# MCU.net
KiCad netlist of a schematic drawn in Altium Designer
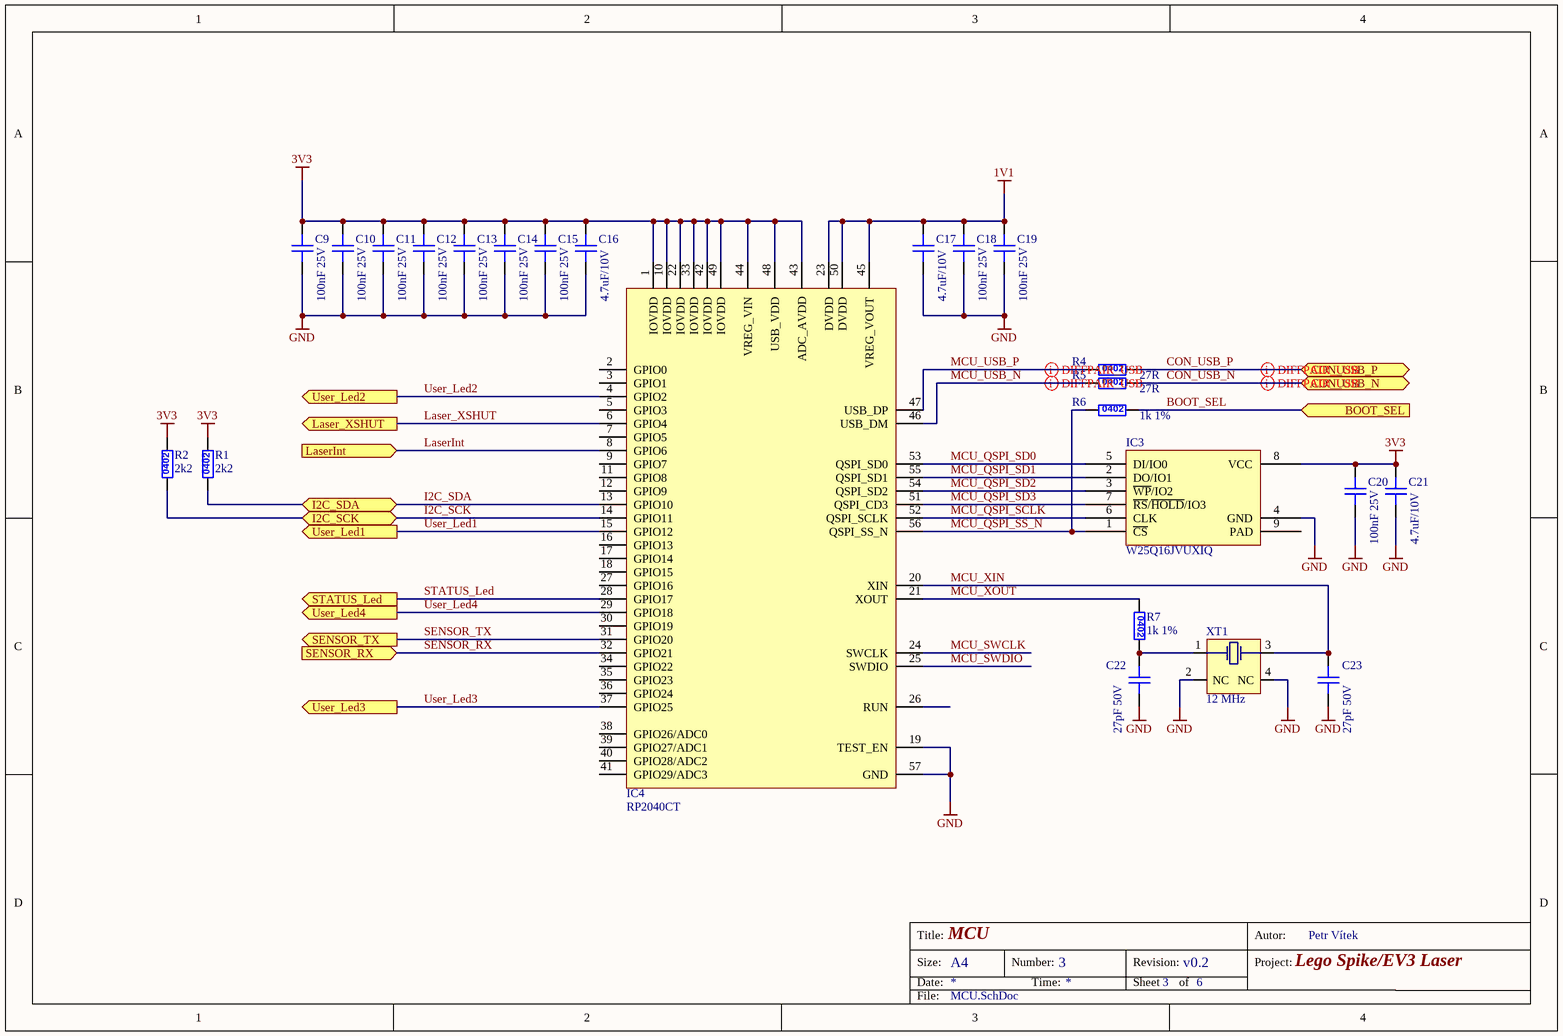
[diagram p0: MCU.SchDoc]

(export (version "E")
  (design (tool "Eeschema 10.0.6"))
  (components
    (comp (ref "C9")
      (value "100nF 25V")
      (footprint "C0402")
      (description "WALSIN - 0402B104K250CT - CAPACITOR, MLCC, X7R, 0.1UF, 25V, 0402")
      (fields (field (name "Comment") "UniversalCapacitor"))
      (libsource (lib "UTBStockLib") (part "UniversalCapacitor"))
    )
    (comp (ref "C10")
      (value "100nF 25V")
      (footprint "C0402")
      (description "WALSIN - 0402B104K250CT - CAPACITOR, MLCC, X7R, 0.1UF, 25V, 0402")
      (fields (field (name "Comment") "UniversalCapacitor"))
      (libsource (lib "UTBStockLib") (part "UniversalCapacitor"))
    )
    (comp (ref "C11")
      (value "100nF 25V")
      (footprint "C0402")
      (description "WALSIN - 0402B104K250CT - CAPACITOR, MLCC, X7R, 0.1UF, 25V, 0402")
      (fields (field (name "Comment") "UniversalCapacitor"))
      (libsource (lib "UTBStockLib") (part "UniversalCapacitor"))
    )
    (comp (ref "C12")
      (value "100nF 25V")
      (footprint "C0402")
      (description "WALSIN - 0402B104K250CT - CAPACITOR, MLCC, X7R, 0.1UF, 25V, 0402")
      (fields (field (name "Comment") "UniversalCapacitor"))
      (libsource (lib "UTBStockLib") (part "UniversalCapacitor"))
    )
    (comp (ref "C13")
      (value "100nF 25V")
      (footprint "C0402")
      (description "WALSIN - 0402B104K250CT - CAPACITOR, MLCC, X7R, 0.1UF, 25V, 0402")
      (fields (field (name "Comment") "UniversalCapacitor"))
      (libsource (lib "UTBStockLib") (part "UniversalCapacitor"))
    )
    (comp (ref "C14")
      (value "100nF 25V")
      (footprint "C0402")
      (description "WALSIN - 0402B104K250CT - CAPACITOR, MLCC, X7R, 0.1UF, 25V, 0402")
      (fields (field (name "Comment") "UniversalCapacitor"))
      (libsource (lib "UTBStockLib") (part "UniversalCapacitor"))
    )
    (comp (ref "C15")
      (value "100nF 25V")
      (footprint "C0402")
      (description "WALSIN - 0402B104K250CT - CAPACITOR, MLCC, X7R, 0.1UF, 25V, 0402")
      (fields (field (name "Comment") "UniversalCapacitor"))
      (libsource (lib "UTBStockLib") (part "UniversalCapacitor"))
    )
    (comp (ref "C16")
      (value "4.7uF/10V")
      (footprint "C0402_big")
      (description "MURATA - GRM155R61A475MEAAD - CAP, MLCC, X5R, 4.7UF, 10V, 0402")
      (libsource (lib "UTBStockLib") (part "UniversalCapacitor"))
    )
    (comp (ref "C17")
      (value "4.7uF/10V")
      (footprint "C0402_big")
      (description "MURATA - GRM155R61A475MEAAD - CAP, MLCC, X5R, 4.7UF, 10V, 0402")
      (libsource (lib "UTBStockLib") (part "UniversalCapacitor"))
    )
    (comp (ref "C18")
      (value "100nF 25V")
      (footprint "C0402")
      (description "WALSIN - 0402B104K250CT - CAPACITOR, MLCC, X7R, 0.1UF, 25V, 0402")
      (fields (field (name "Comment") "UniversalCapacitor"))
      (libsource (lib "UTBStockLib") (part "UniversalCapacitor"))
    )
    (comp (ref "C19")
      (value "100nF 25V")
      (footprint "C0402")
      (description "WALSIN - 0402B104K250CT - CAPACITOR, MLCC, X7R, 0.1UF, 25V, 0402")
      (fields (field (name "Comment") "UniversalCapacitor"))
      (libsource (lib "UTBStockLib") (part "UniversalCapacitor"))
    )
    (comp (ref "C20")
      (value "100nF 25V")
      (footprint "C0402")
      (description "WALSIN - 0402B104K250CT - CAPACITOR, MLCC, X7R, 0.1UF, 25V, 0402")
      (fields (field (name "Comment") "UniversalCapacitor"))
      (libsource (lib "UTBStockLib") (part "UniversalCapacitor"))
    )
    (comp (ref "C21")
      (value "4.7uF/10V")
      (footprint "C0402_big")
      (description "MURATA - GRM155R61A475MEAAD - CAP, MLCC, X5R, 4.7UF, 10V, 0402")
      (libsource (lib "UTBStockLib") (part "UniversalCapacitor"))
    )
    (comp (ref "C22")
      (value "27pF 50V")
      (footprint "C0402")
      (description "WALSIN - 0402N270J500CT - CAPACITOR, MLCC, NP0, 27PF, 50V, 0402")
      (fields (field (name "Comment") "UniversalCapacitor"))
      (libsource (lib "UTBStockLib") (part "UniversalCapacitor"))
    )
    (comp (ref "C23")
      (value "27pF 50V")
      (footprint "C0402")
      (description "WALSIN - 0402N270J500CT - CAPACITOR, MLCC, NP0, 27PF, 50V, 0402")
      (fields (field (name "Comment") "UniversalCapacitor"))
      (libsource (lib "UTBStockLib") (part "UniversalCapacitor"))
    )
    (comp (ref "IC3")
      (value "W25Q16JVUXIQ")
      (footprint "USON-8_3x2")
      (description "Flash NOR spiFlash, 3V, 16M-bit, 4Kb Uniform Sector, DTR")
      (fields (field (name "Comment") "W25Q16JV"))
      (libsource (lib "UTBStockLib") (part "W25Q16JVUXIQ"))
    )
    (comp (ref "IC4")
      (value "RP2040CT")
      (footprint "QFN56")
      (fields (field (name "Comment") "RP2040"))
      (libsource (lib "UTBStockLib") (part "RP2040"))
    )
    (comp (ref "R1")
      (value "2k2")
      (footprint "R0402")
      (description "VISHAY - CRCW04022K20FKED. - RES, THICK FILM, 2K2, 1%, 0.063W, 0402")
      (fields (field (name "Comment") "UniversalResistor0402"))
      (libsource (lib "UTBStockLib") (part "UniversalResistor0402"))
    )
    (comp (ref "R2")
      (value "2k2")
      (footprint "R0402")
      (description "VISHAY - CRCW04022K20FKED. - RES, THICK FILM, 2K2, 1%, 0.063W, 0402")
      (fields (field (name "Comment") "UniversalResistor0402"))
      (libsource (lib "UTBStockLib") (part "UniversalResistor0402"))
    )
    (comp (ref "R4")
      (value "27R")
      (footprint "R0402")
      (fields (field (name "Comment") "UniversalResistor0402"))
      (libsource (lib "UTBStockLib") (part "UniversalResistor0402"))
    )
    (comp (ref "R5")
      (value "27R")
      (footprint "R0402")
      (fields (field (name "Comment") "UniversalResistor0402"))
      (libsource (lib "UTBStockLib") (part "UniversalResistor0402"))
    )
    (comp (ref "R6")
      (value "1k 1%")
      (footprint "R0402")
      (description "VISHAY - CRCW04021K00FKED - RES, THICK FILM, 1K, 1%, 0.063W, 0402")
      (fields (field (name "Comment") "UniversalResistor0402"))
      (libsource (lib "UTBStockLib") (part "UniversalResistor0402"))
    )
    (comp (ref "R7")
      (value "1k 1%")
      (footprint "R0402")
      (description "VISHAY - CRCW04021K00FKED - RES, THICK FILM, 1K, 1%, 0.063W, 0402")
      (fields (field (name "Comment") "UniversalResistor0402"))
      (libsource (lib "UTBStockLib") (part "UniversalResistor0402"))
    )
    (comp (ref "XT1")
      (value "12 MHz")
      (footprint "ABM8")
      (description "Krystaly 12.0 MHZ 18PF 20PPM 120OHM")
      (fields (field (name "Comment") "XTAL-4Pads-2Used"))
      (libsource (lib "UTBStockLib") (part "XTAL-4Pads-2Used"))
    )
  )
  (nets
    (net (code "1") (name "/BOOT_SEL") (class "Default")
      (node (ref "R6") (pin "1") (pinfunction "1_1") (pintype "passive"))
    )
    (net (code "2") (name "/CON_USB_N") (class "Default")
      (node (ref "R5") (pin "1") (pinfunction "1_1") (pintype "passive"))
    )
    (net (code "3") (name "/CON_USB_P") (class "Default")
      (node (ref "R4") (pin "1") (pinfunction "1_1") (pintype "passive"))
    )
    (net (code "4") (name "/I2C_SCK") (class "Default")
      (node (ref "IC4") (pin "14") (pinfunction "GPIO11_14") (pintype "passive"))
      (node (ref "R2") (pin "2") (pinfunction "2_2") (pintype "passive"))
    )
    (net (code "5") (name "/I2C_SDA") (class "Default")
      (node (ref "IC4") (pin "13") (pinfunction "GPIO10_13") (pintype "passive"))
      (node (ref "R1") (pin "2") (pinfunction "2_2") (pintype "passive"))
    )
    (net (code "6") (name "/LaserInt") (class "Default")
      (node (ref "IC4") (pin "8") (pinfunction "GPIO6_8") (pintype "passive"))
    )
    (net (code "7") (name "/Laser_XSHUT") (class "Default")
      (node (ref "IC4") (pin "6") (pinfunction "GPIO4_6") (pintype "passive"))
    )
    (net (code "8") (name "/MCU_QSPI_SCLK") (class "Default")
      (node (ref "IC3") (pin "6") (pinfunction "CLK_6") (pintype "passive"))
      (node (ref "IC4") (pin "52") (pinfunction "QSPI_SCLK_52") (pintype "passive"))
    )
    (net (code "9") (name "/MCU_QSPI_SD0") (class "Default")
      (node (ref "IC3") (pin "5") (pinfunction "DI/IO0_5") (pintype "passive"))
      (node (ref "IC4") (pin "53") (pinfunction "QSPI_SD0_53") (pintype "passive"))
    )
    (net (code "10") (name "/MCU_QSPI_SD1") (class "Default")
      (node (ref "IC3") (pin "2") (pinfunction "DO/IO1_2") (pintype "passive"))
      (node (ref "IC4") (pin "55") (pinfunction "QSPI_SD1_55") (pintype "passive"))
    )
    (net (code "11") (name "/MCU_QSPI_SD2") (class "Default")
      (node (ref "IC3") (pin "3") (pinfunction "~{WP}/IO2_3") (pintype "passive"))
      (node (ref "IC4") (pin "54") (pinfunction "QSPI_SD2_54") (pintype "passive"))
    )
    (net (code "12") (name "/MCU_QSPI_SD3") (class "Default")
      (node (ref "IC3") (pin "7") (pinfunction "~{RS}/~{HOLD}/IO3_7") (pintype "passive"))
      (node (ref "IC4") (pin "51") (pinfunction "QSPI_CD3_51") (pintype "passive"))
    )
    (net (code "13") (name "/MCU_QSPI_SS_N") (class "Default")
      (node (ref "IC3") (pin "1") (pinfunction "~{CS}_1") (pintype "passive"))
      (node (ref "IC4") (pin "56") (pinfunction "QSPI_SS_N_56") (pintype "passive"))
      (node (ref "R6") (pin "2") (pinfunction "2_2") (pintype "passive"))
    )
    (net (code "14") (name "/MCU_SWCLK") (class "Default")
      (node (ref "IC4") (pin "24") (pinfunction "SWCLK_24") (pintype "passive"))
    )
    (net (code "15") (name "/MCU_SWDIO") (class "Default")
      (node (ref "IC4") (pin "25") (pinfunction "SWDIO_25") (pintype "passive"))
    )
    (net (code "16") (name "/MCU_USB_N") (class "Default")
      (node (ref "IC4") (pin "46") (pinfunction "USB_DM_46") (pintype "passive"))
      (node (ref "R5") (pin "2") (pinfunction "2_2") (pintype "passive"))
    )
    (net (code "17") (name "/MCU_USB_P") (class "Default")
      (node (ref "IC4") (pin "47") (pinfunction "USB_DP_47") (pintype "passive"))
      (node (ref "R4") (pin "2") (pinfunction "2_2") (pintype "passive"))
    )
    (net (code "18") (name "/MCU_XIN") (class "Default")
      (node (ref "C23") (pin "1") (pinfunction "1_1") (pintype "passive"))
      (node (ref "IC4") (pin "20") (pinfunction "XIN_20") (pintype "passive"))
      (node (ref "XT1") (pin "3") (pintype "passive"))
    )
    (net (code "19") (name "/MCU_XOUT") (class "Default")
      (node (ref "IC4") (pin "21") (pinfunction "XOUT_21") (pintype "passive"))
      (node (ref "R7") (pin "2") (pinfunction "2_2") (pintype "passive"))
    )
    (net (code "20") (name "/SENSOR_RX") (class "Default")
      (node (ref "IC4") (pin "32") (pinfunction "GPIO21_32") (pintype "passive"))
    )
    (net (code "21") (name "/SENSOR_TX") (class "Default")
      (node (ref "IC4") (pin "31") (pinfunction "GPIO20_31") (pintype "passive"))
    )
    (net (code "22") (name "/STATUS_Led") (class "Default")
      (node (ref "IC4") (pin "28") (pinfunction "GPIO17_28") (pintype "passive"))
    )
    (net (code "23") (name "/User_Led1") (class "Default")
      (node (ref "IC4") (pin "15") (pinfunction "GPIO12_15") (pintype "passive"))
    )
    (net (code "24") (name "/User_Led2") (class "Default")
      (node (ref "IC4") (pin "4") (pinfunction "GPIO2_4") (pintype "passive"))
    )
    (net (code "25") (name "/User_Led3") (class "Default")
      (node (ref "IC4") (pin "37") (pinfunction "GPIO25_37") (pintype "passive"))
    )
    (net (code "26") (name "/User_Led4") (class "Default")
      (node (ref "IC4") (pin "29") (pinfunction "GPIO18_29") (pintype "passive"))
    )
    (net (code "27") (name "1V1") (class "Default")
      (node (ref "C17") (pin "1") (pinfunction "1_1") (pintype "passive"))
      (node (ref "C18") (pin "2") (pinfunction "2_2") (pintype "passive"))
      (node (ref "C19") (pin "2") (pinfunction "2_2") (pintype "passive"))
      (node (ref "IC4") (pin "23") (pinfunction "DVDD_23") (pintype "passive"))
      (node (ref "IC4") (pin "45") (pinfunction "VREG_VOUT_45") (pintype "passive"))
      (node (ref "IC4") (pin "50") (pinfunction "DVDD_50") (pintype "passive"))
    )
    (net (code "28") (name "3V3") (class "Default")
      (node (ref "C10") (pin "2") (pinfunction "2_2") (pintype "passive"))
      (node (ref "C11") (pin "2") (pinfunction "2_2") (pintype "passive"))
      (node (ref "C12") (pin "2") (pinfunction "2_2") (pintype "passive"))
      (node (ref "C13") (pin "2") (pinfunction "2_2") (pintype "passive"))
      (node (ref "C14") (pin "2") (pinfunction "2_2") (pintype "passive"))
      (node (ref "C15") (pin "2") (pinfunction "2_2") (pintype "passive"))
      (node (ref "C16") (pin "1") (pinfunction "1_1") (pintype "passive"))
      (node (ref "C20") (pin "2") (pinfunction "2_2") (pintype "passive"))
      (node (ref "C21") (pin "1") (pinfunction "1_1") (pintype "passive"))
      (node (ref "C9") (pin "2") (pinfunction "2_2") (pintype "passive"))
      (node (ref "IC3") (pin "8") (pinfunction "VCC_8") (pintype "passive"))
      (node (ref "IC4") (pin "1") (pinfunction "IOVDD_1") (pintype "passive"))
      (node (ref "IC4") (pin "10") (pinfunction "IOVDD_10") (pintype "passive"))
      (node (ref "IC4") (pin "22") (pinfunction "IOVDD_22") (pintype "passive"))
      (node (ref "IC4") (pin "33") (pinfunction "IOVDD_33") (pintype "passive"))
      (node (ref "IC4") (pin "42") (pinfunction "IOVDD_42") (pintype "passive"))
      (node (ref "IC4") (pin "43") (pinfunction "ADC_AVDD_43") (pintype "passive"))
      (node (ref "IC4") (pin "44") (pinfunction "VREG_VIN_44") (pintype "passive"))
      (node (ref "IC4") (pin "48") (pinfunction "USB_VDD_48") (pintype "passive"))
      (node (ref "IC4") (pin "49") (pinfunction "IOVDD_49") (pintype "passive"))
      (node (ref "R1") (pin "1") (pinfunction "1_1") (pintype "passive"))
      (node (ref "R2") (pin "1") (pinfunction "1_1") (pintype "passive"))
    )
    (net (code "29") (name "GND") (class "Default")
      (node (ref "C10") (pin "1") (pinfunction "1_1") (pintype "passive"))
      (node (ref "C11") (pin "1") (pinfunction "1_1") (pintype "passive"))
      (node (ref "C12") (pin "1") (pinfunction "1_1") (pintype "passive"))
      (node (ref "C13") (pin "1") (pinfunction "1_1") (pintype "passive"))
      (node (ref "C14") (pin "1") (pinfunction "1_1") (pintype "passive"))
      (node (ref "C15") (pin "1") (pinfunction "1_1") (pintype "passive"))
      (node (ref "C16") (pin "2") (pinfunction "2_2") (pintype "passive"))
      (node (ref "C17") (pin "2") (pinfunction "2_2") (pintype "passive"))
      (node (ref "C18") (pin "1") (pinfunction "1_1") (pintype "passive"))
      (node (ref "C19") (pin "1") (pinfunction "1_1") (pintype "passive"))
      (node (ref "C20") (pin "1") (pinfunction "1_1") (pintype "passive"))
      (node (ref "C21") (pin "2") (pinfunction "2_2") (pintype "passive"))
      (node (ref "C22") (pin "2") (pinfunction "2_2") (pintype "passive"))
      (node (ref "C23") (pin "2") (pinfunction "2_2") (pintype "passive"))
      (node (ref "C9") (pin "1") (pinfunction "1_1") (pintype "passive"))
      (node (ref "IC3") (pin "4") (pinfunction "GND_4") (pintype "passive"))
      (node (ref "IC4") (pin "19") (pinfunction "TEST_EN_19") (pintype "passive"))
      (node (ref "IC4") (pin "57") (pinfunction "GND_57") (pintype "passive"))
      (node (ref "XT1") (pin "2") (pinfunction "NC_2") (pintype "passive"))
      (node (ref "XT1") (pin "4") (pinfunction "NC_4") (pintype "passive"))
    )
    (net (code "30") (name "Net-(C22-Pad1)") (class "Default")
      (node (ref "C22") (pin "1") (pinfunction "1_1") (pintype "passive"))
      (node (ref "R7") (pin "1") (pinfunction "1_1") (pintype "passive"))
      (node (ref "XT1") (pin "1") (pintype "passive"))
    )
    (net (code "31") (name "unconnected-(IC3-PAD-Pad9)") (class "Default")
      (node (ref "IC3") (pin "9") (pinfunction "PAD_9") (pintype "passive"))
    )
    (net (code "32") (name "unconnected-(IC4-GPIO0-Pad2)") (class "Default")
      (node (ref "IC4") (pin "2") (pinfunction "GPIO0_2") (pintype "passive"))
    )
    (net (code "33") (name "unconnected-(IC4-GPIO1-Pad3)") (class "Default")
      (node (ref "IC4") (pin "3") (pinfunction "GPIO1_3") (pintype "passive"))
    )
    (net (code "34") (name "unconnected-(IC4-GPIO3-Pad5)") (class "Default")
      (node (ref "IC4") (pin "5") (pinfunction "GPIO3_5") (pintype "passive"))
    )
    (net (code "35") (name "unconnected-(IC4-GPIO5-Pad7)") (class "Default")
      (node (ref "IC4") (pin "7") (pinfunction "GPIO5_7") (pintype "passive"))
    )
    (net (code "36") (name "unconnected-(IC4-GPIO7-Pad9)") (class "Default")
      (node (ref "IC4") (pin "9") (pinfunction "GPIO7_9") (pintype "passive"))
    )
    (net (code "37") (name "unconnected-(IC4-GPIO8-Pad11)") (class "Default")
      (node (ref "IC4") (pin "11") (pinfunction "GPIO8_11") (pintype "passive"))
    )
    (net (code "38") (name "unconnected-(IC4-GPIO9-Pad12)") (class "Default")
      (node (ref "IC4") (pin "12") (pinfunction "GPIO9_12") (pintype "passive"))
    )
    (net (code "39") (name "unconnected-(IC4-GPIO13-Pad16)") (class "Default")
      (node (ref "IC4") (pin "16") (pinfunction "GPIO13_16") (pintype "passive"))
    )
    (net (code "40") (name "unconnected-(IC4-GPIO14-Pad17)") (class "Default")
      (node (ref "IC4") (pin "17") (pinfunction "GPIO14_17") (pintype "passive"))
    )
    (net (code "41") (name "unconnected-(IC4-GPIO15-Pad18)") (class "Default")
      (node (ref "IC4") (pin "18") (pinfunction "GPIO15_18") (pintype "passive"))
    )
    (net (code "42") (name "unconnected-(IC4-GPIO16-Pad27)") (class "Default")
      (node (ref "IC4") (pin "27") (pinfunction "GPIO16_27") (pintype "passive"))
    )
    (net (code "43") (name "unconnected-(IC4-GPIO19-Pad30)") (class "Default")
      (node (ref "IC4") (pin "30") (pinfunction "GPIO19_30") (pintype "passive"))
    )
    (net (code "44") (name "unconnected-(IC4-GPIO22-Pad34)") (class "Default")
      (node (ref "IC4") (pin "34") (pinfunction "GPIO22_34") (pintype "passive"))
    )
    (net (code "45") (name "unconnected-(IC4-GPIO23-Pad35)") (class "Default")
      (node (ref "IC4") (pin "35") (pinfunction "GPIO23_35") (pintype "passive"))
    )
    (net (code "46") (name "unconnected-(IC4-GPIO24-Pad36)") (class "Default")
      (node (ref "IC4") (pin "36") (pinfunction "GPIO24_36") (pintype "passive"))
    )
    (net (code "47") (name "unconnected-(IC4-GPIO26{slash}ADC0-Pad38)") (class "Default")
      (node (ref "IC4") (pin "38") (pinfunction "GPIO26/ADC0_38") (pintype "passive"))
    )
    (net (code "48") (name "unconnected-(IC4-GPIO27{slash}ADC1-Pad39)") (class "Default")
      (node (ref "IC4") (pin "39") (pinfunction "GPIO27/ADC1_39") (pintype "passive"))
    )
    (net (code "49") (name "unconnected-(IC4-GPIO28{slash}ADC2-Pad40)") (class "Default")
      (node (ref "IC4") (pin "40") (pinfunction "GPIO28/ADC2_40") (pintype "passive"))
    )
    (net (code "50") (name "unconnected-(IC4-GPIO29{slash}ADC3-Pad41)") (class "Default")
      (node (ref "IC4") (pin "41") (pinfunction "GPIO29/ADC3_41") (pintype "passive"))
    )
    (net (code "51") (name "unconnected-(IC4-RUN-Pad26)") (class "Default")
      (node (ref "IC4") (pin "26") (pinfunction "RUN_26") (pintype "passive"))
    )
  )
)
